# GhostbustersR1-FIXED.net
KiCad netlist of a schematic drawn in EAGLE
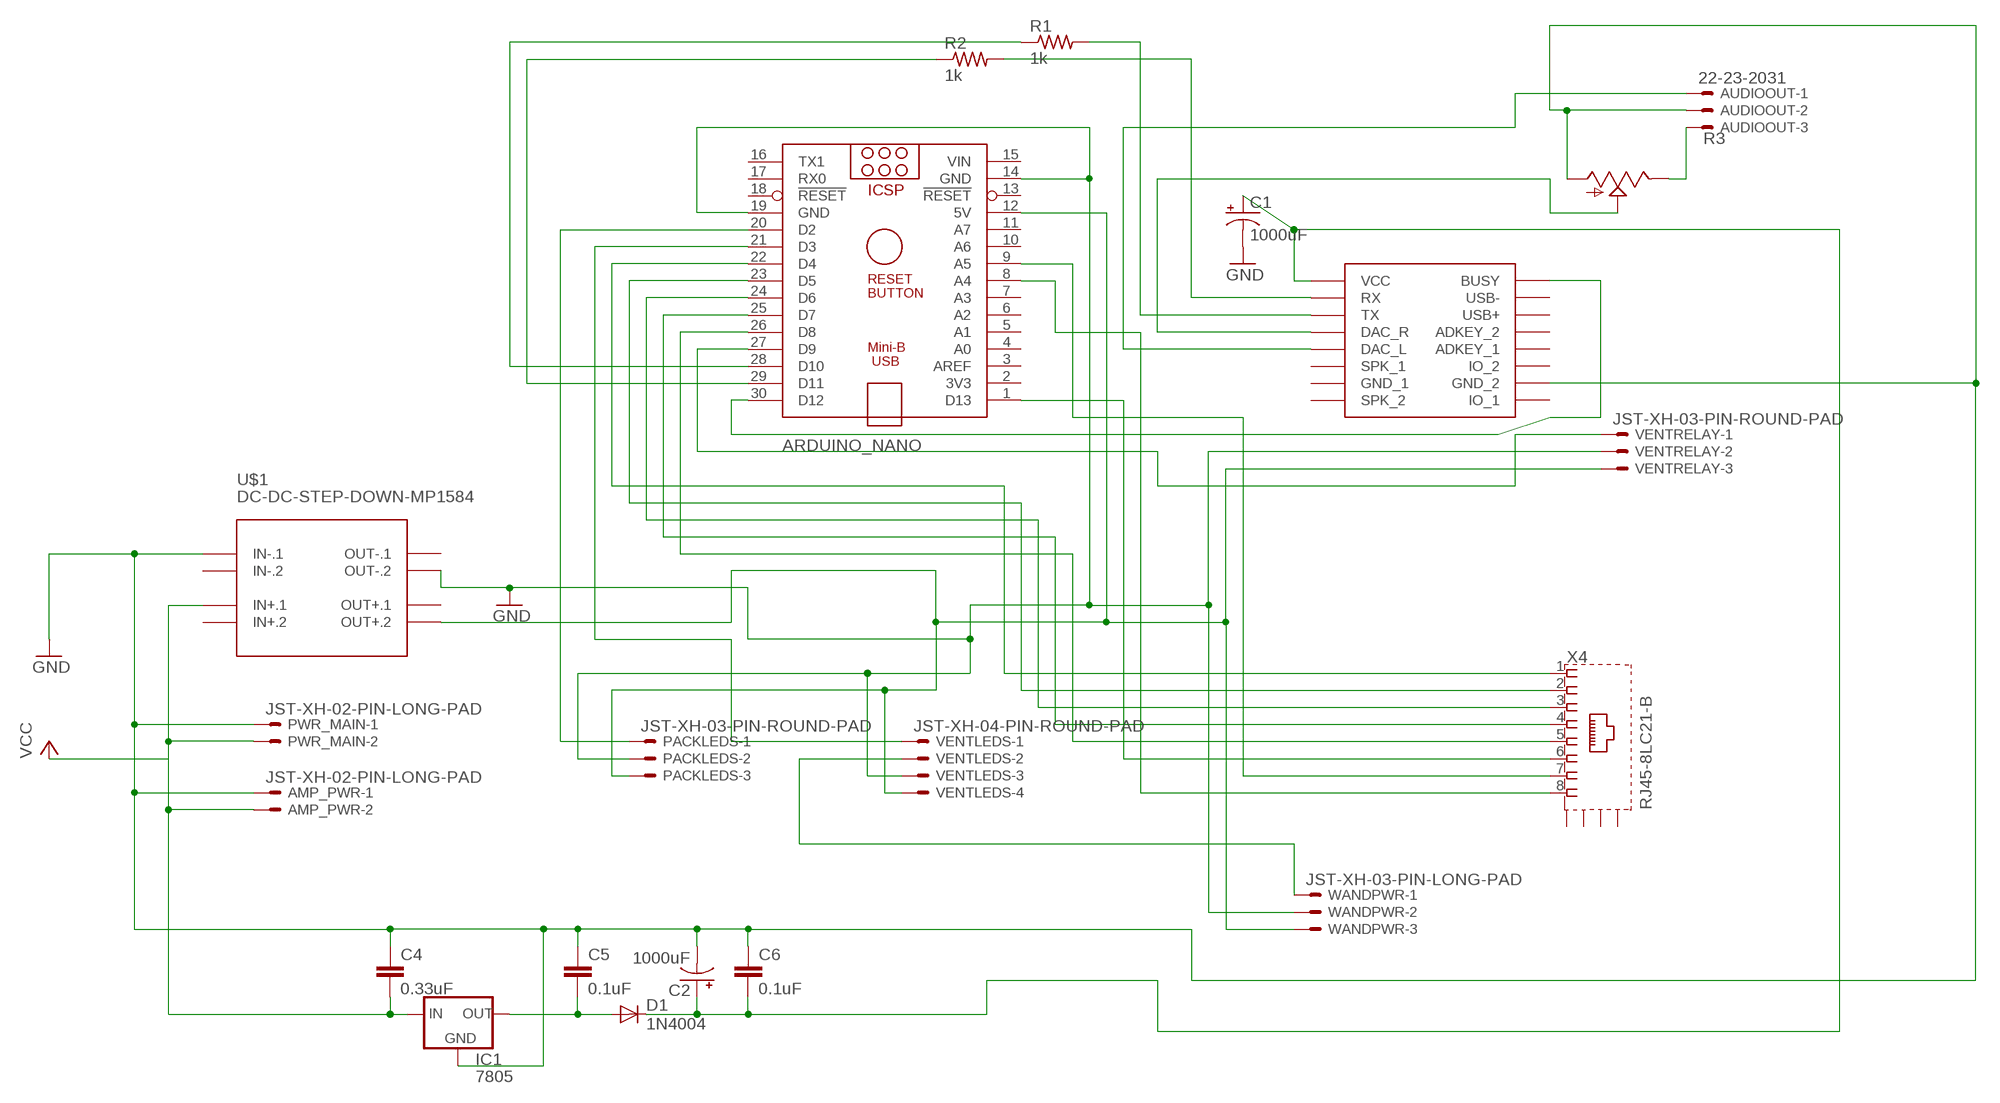
[diagram p0: schematic, sheet 1]

(export (version "E")
  (design (tool "Eeschema 10.0.6"))
  (components
    (comp (ref "AMP_PWR")
      (value "JST-XH-02-PIN-LONG-PAD")
      (footprint "eagle-import:JST-XH-02-PACKAGE-LONG-PAD")
      (libsource (lib "eagle-import") (part "JST-XH-02-PIN-LONG-PAD"))
    )
    (comp (ref "ARDUINO_NANO")
      (value "ARDUINO_NANO")
      (footprint "eagle-import:ARDUINO_NANO")
      (libsource (lib "eagle-import") (part "ARDUINO_NANO"))
    )
    (comp (ref "AUDIOOUT")
      (value "22-23-2031")
      (footprint "eagle-import:22-23-2031")
      (fields (field (name "MF") "MOLEX"))
      (libsource (lib "eagle-import") (part "22-23-2031"))
    )
    (comp (ref "C1")
      (value "1000uF")
      (footprint "eagle-import:E3,5-8")
      (libsource (lib "eagle-import") (part "CPOL-USE3.5-8"))
    )
    (comp (ref "C2")
      (value "1000uF")
      (footprint "eagle-import:E3,5-8")
      (libsource (lib "eagle-import") (part "CPOL-USE3.5-8"))
    )
    (comp (ref "C4")
      (value "0.33uF")
      (footprint "eagle-import:C2.5-4")
      (libsource (lib "eagle-import") (part "C2.5/4"))
    )
    (comp (ref "C5")
      (value "0.1uF")
      (footprint "eagle-import:C2.5-4")
      (libsource (lib "eagle-import") (part "C2.5/4"))
    )
    (comp (ref "C6")
      (value "0.1uF")
      (footprint "eagle-import:C2.5-4")
      (libsource (lib "eagle-import") (part "C2.5/4"))
    )
    (comp (ref "D1")
      (value "1N4004")
      (footprint "eagle-import:DO41-10")
      (libsource (lib "eagle-import") (part "1N4004"))
    )
    (comp (ref "DFPLAYER")
      (value "DFPLAYER")
      (footprint "eagle-import:DFPLAYER")
      (libsource (lib "eagle-import") (part "DFPLAYER"))
    )
    (comp (ref "IC1")
      (value "7805")
      (footprint "eagle-import:78MXXS")
      (libsource (lib "eagle-import") (part "78MXXS"))
    )
    (comp (ref "PACKLEDS")
      (value "JST-XH-03-PIN-ROUND-PAD")
      (footprint "eagle-import:JST-XH-03-PACKAGE-ROUND-PAD")
      (libsource (lib "eagle-import") (part "JST-XH-03-PIN-ROUND-PAD"))
    )
    (comp (ref "PWR_MAIN")
      (value "JST-XH-02-PIN-LONG-PAD")
      (footprint "eagle-import:JST-XH-02-PACKAGE-LONG-PAD")
      (libsource (lib "eagle-import") (part "JST-XH-02-PIN-LONG-PAD"))
    )
    (comp (ref "R1")
      (value "1k")
      (footprint "eagle-import:0207_12")
      (libsource (lib "eagle-import") (part "R-US_0207/12"))
    )
    (comp (ref "R2")
      (value "1k")
      (footprint "eagle-import:0207_12")
      (libsource (lib "eagle-import") (part "R-US_0207/12"))
    )
    (comp (ref "R3")
      (value "TRIM_US-B64Y")
      (footprint "eagle-import:B64Y")
      (libsource (lib "eagle-import") (part "TRIM_US-B64Y"))
    )
    (comp (ref "U$1")
      (value "DC-DC-STEP-DOWN-MP1584")
      (footprint "eagle-import:DC-DC-STEP-DOWN-MP1584")
      (libsource (lib "eagle-import") (part "DC-DC-STEP-DOWN-MP1584"))
    )
    (comp (ref "VENTLEDS")
      (value "JST-XH-04-PIN-ROUND-PAD")
      (footprint "eagle-import:JST-XH-04-PACKAGE-ROUND-PAD")
      (libsource (lib "eagle-import") (part "JST-XH-04-PIN-ROUND-PAD"))
    )
    (comp (ref "VENTRELAY")
      (value "JST-XH-03-PIN-ROUND-PAD")
      (footprint "eagle-import:JST-XH-03-PACKAGE-ROUND-PAD")
      (libsource (lib "eagle-import") (part "JST-XH-03-PIN-ROUND-PAD"))
    )
    (comp (ref "WANDPWR")
      (value "JST-XH-03-PIN-LONG-PAD")
      (footprint "eagle-import:JST-XH-03-PACKAGE-LONG-PAD")
      (libsource (lib "eagle-import") (part "JST-XH-03-PIN-LONG-PAD"))
    )
    (comp (ref "X4")
      (value "RJ45-8LC21-B")
      (footprint "eagle-import:RJ45-SHIELD1")
      (libsource (lib "eagle-import") (part "RJ4521-B-8LC"))
    )
  )
  (nets
    (net (code "1") (name "/VIN") (class "Default")
      (node (ref "ARDUINO_NANO") (pin "15") (pinfunction "VIN_15") (pintype "power_in"))
    )
    (net (code "2") (name "GND") (class "Default")
      (node (ref "AMP_PWR") (pin "1") (pinfunction "S_1") (pintype "passive"))
      (node (ref "ARDUINO_NANO") (pin "14") (pinfunction "GND_14") (pintype "power_in"))
      (node (ref "ARDUINO_NANO") (pin "19") (pinfunction "GND_19") (pintype "power_in"))
      (node (ref "AUDIOOUT") (pin "2") (pinfunction "S_2") (pintype "passive"))
      (node (ref "C1") (pin "-") (pinfunction "-_-") (pintype "passive"))
      (node (ref "C2") (pin "-") (pinfunction "-_-") (pintype "passive"))
      (node (ref "C4") (pin "1") (pinfunction "1_1") (pintype "passive"))
      (node (ref "C5") (pin "1") (pinfunction "1_1") (pintype "passive"))
      (node (ref "C6") (pin "1") (pinfunction "1_1") (pintype "passive"))
      (node (ref "DFPLAYER") (pin "GND_2") (pinfunction "GND_2_GND_2") (pintype "bidirectional"))
      (node (ref "IC1") (pin "GND") (pinfunction "GND_GND") (pintype "input"))
      (node (ref "PACKLEDS") (pin "2") (pinfunction "S_2") (pintype "passive"))
      (node (ref "PWR_MAIN") (pin "1") (pinfunction "S_1") (pintype "passive"))
      (node (ref "R3") (pin "A") (pinfunction "A_A") (pintype "passive"))
      (node (ref "U$1") (pin "IN-.1") (pinfunction "IN-.1_IN-.1") (pintype "bidirectional"))
      (node (ref "U$1") (pin "OUT-.2") (pinfunction "OUT-.2_OUT-.2") (pintype "bidirectional"))
      (node (ref "VENTLEDS") (pin "3") (pinfunction "S_3") (pintype "passive"))
      (node (ref "VENTRELAY") (pin "2") (pinfunction "S_2") (pintype "passive"))
      (node (ref "WANDPWR") (pin "2") (pinfunction "S_2") (pintype "passive"))
    )
    (net (code "3") (name "Net-(ARDUINO_NANO-5V)") (class "Default")
      (node (ref "ARDUINO_NANO") (pin "12") (pinfunction "5V_12") (pintype "power_in"))
      (node (ref "PACKLEDS") (pin "3") (pinfunction "S_3") (pintype "passive"))
      (node (ref "U$1") (pin "OUT+.2") (pinfunction "OUT+.2_OUT+.2") (pintype "bidirectional"))
      (node (ref "VENTLEDS") (pin "4") (pinfunction "S_4") (pintype "passive"))
      (node (ref "VENTRELAY") (pin "3") (pinfunction "S_3") (pintype "passive"))
      (node (ref "WANDPWR") (pin "3") (pinfunction "S_3") (pintype "passive"))
    )
    (net (code "4") (name "Net-(ARDUINO_NANO-A4)") (class "Default")
      (node (ref "ARDUINO_NANO") (pin "8") (pinfunction "A4_8") (pintype "bidirectional"))
      (node (ref "X4") (pin "8") (pinfunction "8_8") (pintype "passive"))
    )
    (net (code "5") (name "Net-(ARDUINO_NANO-A5)") (class "Default")
      (node (ref "ARDUINO_NANO") (pin "9") (pinfunction "A5_9") (pintype "bidirectional"))
      (node (ref "X4") (pin "7") (pinfunction "7_7") (pintype "passive"))
    )
    (net (code "6") (name "Net-(ARDUINO_NANO-D2)") (class "Default")
      (node (ref "ARDUINO_NANO") (pin "20") (pinfunction "D2_20") (pintype "bidirectional"))
      (node (ref "PACKLEDS") (pin "1") (pinfunction "S_1") (pintype "passive"))
    )
    (net (code "7") (name "Net-(ARDUINO_NANO-D3)") (class "Default")
      (node (ref "ARDUINO_NANO") (pin "21") (pinfunction "D3_21") (pintype "bidirectional"))
      (node (ref "VENTLEDS") (pin "1") (pinfunction "S_1") (pintype "passive"))
    )
    (net (code "8") (name "Net-(ARDUINO_NANO-D4)") (class "Default")
      (node (ref "ARDUINO_NANO") (pin "22") (pinfunction "D4_22") (pintype "bidirectional"))
      (node (ref "X4") (pin "1") (pinfunction "1_1") (pintype "passive"))
    )
    (net (code "9") (name "Net-(ARDUINO_NANO-D5)") (class "Default")
      (node (ref "ARDUINO_NANO") (pin "23") (pinfunction "D5_23") (pintype "bidirectional"))
      (node (ref "X4") (pin "2") (pinfunction "2_2") (pintype "passive"))
    )
    (net (code "10") (name "Net-(ARDUINO_NANO-D6)") (class "Default")
      (node (ref "ARDUINO_NANO") (pin "24") (pinfunction "D6_24") (pintype "bidirectional"))
      (node (ref "X4") (pin "3") (pinfunction "3_3") (pintype "passive"))
    )
    (net (code "11") (name "Net-(ARDUINO_NANO-D7)") (class "Default")
      (node (ref "ARDUINO_NANO") (pin "25") (pinfunction "D7_25") (pintype "bidirectional"))
      (node (ref "X4") (pin "4") (pinfunction "4_4") (pintype "passive"))
    )
    (net (code "12") (name "Net-(ARDUINO_NANO-D8)") (class "Default")
      (node (ref "ARDUINO_NANO") (pin "26") (pinfunction "D8_26") (pintype "bidirectional"))
      (node (ref "X4") (pin "5") (pinfunction "5_5") (pintype "passive"))
    )
    (net (code "13") (name "Net-(ARDUINO_NANO-D9)") (class "Default")
      (node (ref "ARDUINO_NANO") (pin "27") (pinfunction "D9_27") (pintype "bidirectional"))
      (node (ref "VENTRELAY") (pin "1") (pinfunction "S_1") (pintype "passive"))
    )
    (net (code "14") (name "Net-(ARDUINO_NANO-D10)") (class "Default")
      (node (ref "ARDUINO_NANO") (pin "28") (pinfunction "D10_28") (pintype "bidirectional"))
      (node (ref "R1") (pin "1") (pinfunction "1_1") (pintype "passive"))
    )
    (net (code "15") (name "Net-(ARDUINO_NANO-D11)") (class "Default")
      (node (ref "ARDUINO_NANO") (pin "29") (pinfunction "D11_29") (pintype "bidirectional"))
      (node (ref "R2") (pin "1") (pinfunction "1_1") (pintype "passive"))
    )
    (net (code "16") (name "Net-(ARDUINO_NANO-D12)") (class "Default")
      (node (ref "ARDUINO_NANO") (pin "30") (pinfunction "D12_30") (pintype "bidirectional"))
      (node (ref "DFPLAYER") (pin "BUSY") (pinfunction "BUSY_BUSY") (pintype "bidirectional"))
    )
    (net (code "17") (name "Net-(ARDUINO_NANO-D13)") (class "Default")
      (node (ref "ARDUINO_NANO") (pin "1") (pinfunction "D13_1") (pintype "bidirectional"))
      (node (ref "X4") (pin "6") (pinfunction "6_6") (pintype "passive"))
    )
    (net (code "18") (name "Net-(AUDIOOUTA-S)") (class "Default")
      (node (ref "AUDIOOUT") (pin "1") (pinfunction "S_1") (pintype "passive"))
      (node (ref "DFPLAYER") (pin "DAC_L") (pinfunction "DAC_L_DAC_L") (pintype "bidirectional"))
    )
    (net (code "19") (name "Net-(AUDIOOUTC-S)") (class "Default")
      (node (ref "AUDIOOUT") (pin "3") (pinfunction "S_3") (pintype "passive"))
      (node (ref "R3") (pin "E") (pinfunction "E_E") (pintype "passive"))
    )
    (net (code "20") (name "Net-(C1-Pad+)") (class "Default")
      (node (ref "C1") (pin "+") (pinfunction "+_+") (pintype "passive"))
      (node (ref "C2") (pin "+") (pinfunction "+_+") (pintype "passive"))
      (node (ref "C6") (pin "2") (pinfunction "2_2") (pintype "passive"))
      (node (ref "D1") (pin "C") (pinfunction "C_C") (pintype "passive"))
      (node (ref "DFPLAYER") (pin "VCC") (pinfunction "VCC_VCC") (pintype "bidirectional"))
    )
    (net (code "21") (name "Net-(C5-Pad2)") (class "Default")
      (node (ref "C5") (pin "2") (pinfunction "2_2") (pintype "passive"))
      (node (ref "D1") (pin "A") (pinfunction "A_A") (pintype "passive"))
      (node (ref "IC1") (pin "OUT") (pinfunction "OUT_OUT") (pintype "passive"))
    )
    (net (code "22") (name "Net-(DFPLAYER-PadDAC_R)") (class "Default")
      (node (ref "DFPLAYER") (pin "DAC_R") (pinfunction "DAC_R_DAC_R") (pintype "bidirectional"))
      (node (ref "R3") (pin "S") (pinfunction "S_S") (pintype "passive"))
    )
    (net (code "23") (name "Net-(DFPLAYER-PadRX)") (class "Default")
      (node (ref "DFPLAYER") (pin "RX") (pinfunction "RX_RX") (pintype "bidirectional"))
      (node (ref "R2") (pin "2") (pinfunction "2_2") (pintype "passive"))
    )
    (net (code "24") (name "Net-(DFPLAYER-PadTX)") (class "Default")
      (node (ref "DFPLAYER") (pin "TX") (pinfunction "TX_TX") (pintype "bidirectional"))
      (node (ref "R1") (pin "2") (pinfunction "2_2") (pintype "passive"))
    )
    (net (code "25") (name "Net-(VENTLEDSB-S)") (class "Default")
      (node (ref "VENTLEDS") (pin "2") (pinfunction "S_2") (pintype "passive"))
      (node (ref "WANDPWR") (pin "1") (pinfunction "S_1") (pintype "passive"))
    )
    (net (code "26") (name "VCC") (class "Default")
      (node (ref "AMP_PWR") (pin "2") (pinfunction "S_2") (pintype "passive"))
      (node (ref "C4") (pin "2") (pinfunction "2_2") (pintype "passive"))
      (node (ref "IC1") (pin "IN") (pinfunction "IN_IN") (pintype "input"))
      (node (ref "PWR_MAIN") (pin "2") (pinfunction "S_2") (pintype "passive"))
      (node (ref "U$1") (pin "IN+.1") (pinfunction "IN+.1_IN+.1") (pintype "bidirectional"))
    )
    (net (code "27") (name "unconnected-(ARDUINO_NANO-3V3-Pad2)") (class "Default")
      (node (ref "ARDUINO_NANO") (pin "2") (pinfunction "3V3_2") (pintype "output"))
    )
    (net (code "28") (name "unconnected-(ARDUINO_NANO-A0-Pad4)") (class "Default")
      (node (ref "ARDUINO_NANO") (pin "4") (pinfunction "A0_4") (pintype "bidirectional"))
    )
    (net (code "29") (name "unconnected-(ARDUINO_NANO-A1-Pad5)") (class "Default")
      (node (ref "ARDUINO_NANO") (pin "5") (pinfunction "A1_5") (pintype "bidirectional"))
    )
    (net (code "30") (name "unconnected-(ARDUINO_NANO-A2-Pad6)") (class "Default")
      (node (ref "ARDUINO_NANO") (pin "6") (pinfunction "A2_6") (pintype "bidirectional"))
    )
    (net (code "31") (name "unconnected-(ARDUINO_NANO-A3-Pad7)") (class "Default")
      (node (ref "ARDUINO_NANO") (pin "7") (pinfunction "A3_7") (pintype "bidirectional"))
    )
    (net (code "32") (name "unconnected-(ARDUINO_NANO-A6-Pad10)") (class "Default")
      (node (ref "ARDUINO_NANO") (pin "10") (pinfunction "A6_10") (pintype "bidirectional"))
    )
    (net (code "33") (name "unconnected-(ARDUINO_NANO-A7-Pad11)") (class "Default")
      (node (ref "ARDUINO_NANO") (pin "11") (pinfunction "A7_11") (pintype "bidirectional"))
    )
    (net (code "34") (name "unconnected-(ARDUINO_NANO-AREF-Pad3)") (class "Default")
      (node (ref "ARDUINO_NANO") (pin "3") (pinfunction "AREF_3") (pintype "input"))
    )
    (net (code "35") (name "unconnected-(ARDUINO_NANO-RX0-Pad17)") (class "Default")
      (node (ref "ARDUINO_NANO") (pin "17") (pinfunction "RX0_17") (pintype "bidirectional"))
    )
    (net (code "36") (name "unconnected-(ARDUINO_NANO-TX1-Pad16)") (class "Default")
      (node (ref "ARDUINO_NANO") (pin "16") (pinfunction "TX1_16") (pintype "bidirectional"))
    )
    (net (code "37") (name "unconnected-(ARDUINO_NANO-~{RESET}-Pad13)") (class "Default")
      (node (ref "ARDUINO_NANO") (pin "13") (pinfunction "~{RESET}_13") (pintype "input"))
    )
    (net (code "38") (name "unconnected-(ARDUINO_NANO-~{RESET}-Pad18)") (class "Default")
      (node (ref "ARDUINO_NANO") (pin "18") (pinfunction "~{RESET}_18") (pintype "input"))
    )
    (net (code "39") (name "unconnected-(DFPLAYER-ADKEY_1-PadADKEY1)") (class "Default")
      (node (ref "DFPLAYER") (pin "ADKEY1") (pinfunction "ADKEY_1_ADKEY1") (pintype "bidirectional"))
    )
    (net (code "40") (name "unconnected-(DFPLAYER-ADKEY_2-PadADKEY2)") (class "Default")
      (node (ref "DFPLAYER") (pin "ADKEY2") (pinfunction "ADKEY_2_ADKEY2") (pintype "bidirectional"))
    )
    (net (code "41") (name "unconnected-(DFPLAYER-IO_1-PadIO1)") (class "Default")
      (node (ref "DFPLAYER") (pin "IO1") (pinfunction "IO_1_IO1") (pintype "bidirectional"))
    )
    (net (code "42") (name "unconnected-(DFPLAYER-IO_2-PadIO2)") (class "Default")
      (node (ref "DFPLAYER") (pin "IO2") (pinfunction "IO_2_IO2") (pintype "bidirectional"))
    )
    (net (code "43") (name "unconnected-(DFPLAYER-PadGND_1)") (class "Default")
      (node (ref "DFPLAYER") (pin "GND_1") (pinfunction "GND_1_GND_1") (pintype "bidirectional"))
    )
    (net (code "44") (name "unconnected-(DFPLAYER-PadUSB+)") (class "Default")
      (node (ref "DFPLAYER") (pin "USB+") (pinfunction "USB+_USB+") (pintype "bidirectional"))
    )
    (net (code "45") (name "unconnected-(DFPLAYER-PadUSB-)") (class "Default")
      (node (ref "DFPLAYER") (pin "USB-") (pinfunction "USB-_USB-") (pintype "bidirectional"))
    )
    (net (code "46") (name "unconnected-(DFPLAYER-SPK_1-PadSPK1)") (class "Default")
      (node (ref "DFPLAYER") (pin "SPK1") (pinfunction "SPK_1_SPK1") (pintype "bidirectional"))
    )
    (net (code "47") (name "unconnected-(DFPLAYER-SPK_2-PadSPK2)") (class "Default")
      (node (ref "DFPLAYER") (pin "SPK2") (pinfunction "SPK_2_SPK2") (pintype "bidirectional"))
    )
    (net (code "48") (name "unconnected-(U$1-PadIN+.2)") (class "Default")
      (node (ref "U$1") (pin "IN+.2") (pinfunction "IN+.2_IN+.2") (pintype "bidirectional"))
    )
    (net (code "49") (name "unconnected-(U$1-PadIN-.2)") (class "Default")
      (node (ref "U$1") (pin "IN-.2") (pinfunction "IN-.2_IN-.2") (pintype "bidirectional"))
    )
    (net (code "50") (name "unconnected-(U$1-PadOUT+.1)") (class "Default")
      (node (ref "U$1") (pin "OUT+.1") (pinfunction "OUT+.1_OUT+.1") (pintype "bidirectional"))
    )
    (net (code "51") (name "unconnected-(U$1-PadOUT-.1)") (class "Default")
      (node (ref "U$1") (pin "OUT-.1") (pinfunction "OUT-.1_OUT-.1") (pintype "bidirectional"))
    )
    (net (code "52") (name "unconnected-(X4-S-PadS1)") (class "Default")
      (node (ref "X4") (pin "S1") (pinfunction "S_S1") (pintype "passive"))
    )
    (net (code "53") (name "unconnected-(X4-S-PadS2)") (class "Default")
      (node (ref "X4") (pin "S2") (pinfunction "S_S2") (pintype "passive"))
    )
    (net (code "54") (name "unconnected-(X4-S-PadS3)") (class "Default")
      (node (ref "X4") (pin "S3") (pinfunction "S_S3") (pintype "passive"))
    )
    (net (code "55") (name "unconnected-(X4-S-PadS4)") (class "Default")
      (node (ref "X4") (pin "S4") (pinfunction "S_S4") (pintype "passive"))
    )
  )
)
